# DRV8871.net
KiCad netlist of a schematic drawn in EAGLE
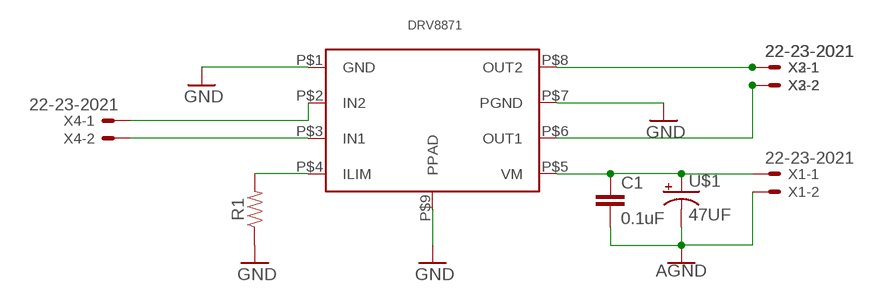
[diagram p0: schematic, sheet 1]

(export (version "E")
  (design (tool "Eeschema 10.0.6"))
  (components
    (comp (ref "C1")
      (value "0.1uF")
      (footprint "eagle-import:0402")
      (libsource (lib "eagle-import") (part "0.1UF-0402-16V-10%"))
    )
    (comp (ref "R1")
      (value "RESISTOR0402")
      (footprint "eagle-import:0402")
      (libsource (lib "eagle-import") (part "RESISTOR0402"))
    )
    (comp (ref "U$1")
      (value "47UF")
      (footprint "eagle-import:UCM1C470MCL1GS")
      (libsource (lib "eagle-import") (part "47UF"))
    )
    (comp (ref "U1")
      (value "DRV8871")
      (footprint "eagle-import:DDA(R-PDSO-G8)")
      (libsource (lib "eagle-import") (part "DRV8871"))
    )
    (comp (ref "X1")
      (value "22-23-2021")
      (footprint "eagle-import:22-23-2021")
      (fields (field (name "MF") "MOLEX"))
      (libsource (lib "eagle-import") (part "22-23-2021"))
    )
    (comp (ref "X2")
      (value "22-23-2021")
      (footprint "eagle-import:22-23-2021")
      (fields (field (name "MF") "MOLEX"))
      (libsource (lib "eagle-import") (part "22-23-2021"))
    )
    (comp (ref "X3")
      (value "22-23-2021")
      (footprint "eagle-import:22-23-2021")
      (fields (field (name "MF") "MOLEX"))
      (libsource (lib "eagle-import") (part "22-23-2021"))
    )
    (comp (ref "X4")
      (value "22-23-2021")
      (footprint "eagle-import:22-23-2021")
      (fields (field (name "MF") "MOLEX"))
      (libsource (lib "eagle-import") (part "22-23-2021"))
    )
  )
  (nets
    (net (code "1") (name "AGND") (class "Default")
      (node (ref "C1") (pin "2") (pinfunction "2_2") (pintype "passive"))
      (node (ref "U$1") (pin "P$2") (pinfunction "-_P$2") (pintype "passive"))
      (node (ref "X1") (pin "2") (pinfunction "S_2") (pintype "passive"))
    )
    (net (code "2") (name "GND") (class "Default")
      (node (ref "R1") (pin "1") (pinfunction "1_1") (pintype "passive"))
      (node (ref "U1") (pin "P$1") (pinfunction "GND_P$1") (pintype "bidirectional"))
      (node (ref "U1") (pin "P$7") (pinfunction "PGND_P$7") (pintype "bidirectional"))
      (node (ref "U1") (pin "P$9") (pinfunction "PPAD_P$9") (pintype "bidirectional"))
    )
    (net (code "3") (name "Net-(U$1-+)") (class "Default")
      (node (ref "C1") (pin "1") (pinfunction "1_1") (pintype "passive"))
      (node (ref "U$1") (pin "P$1") (pinfunction "+_P$1") (pintype "passive"))
      (node (ref "U1") (pin "P$5") (pinfunction "VM_P$5") (pintype "bidirectional"))
      (node (ref "X1") (pin "1") (pinfunction "S_1") (pintype "passive"))
    )
    (net (code "4") (name "Net-(U1-ILIM)") (class "Default")
      (node (ref "R1") (pin "2") (pinfunction "2_2") (pintype "passive"))
      (node (ref "U1") (pin "P$4") (pinfunction "ILIM_P$4") (pintype "bidirectional"))
    )
    (net (code "5") (name "Net-(U1-IN1)") (class "Default")
      (node (ref "U1") (pin "P$3") (pinfunction "IN1_P$3") (pintype "bidirectional"))
      (node (ref "X4") (pin "2") (pinfunction "S_2") (pintype "passive"))
    )
    (net (code "6") (name "Net-(U1-IN2)") (class "Default")
      (node (ref "U1") (pin "P$2") (pinfunction "IN2_P$2") (pintype "bidirectional"))
      (node (ref "X4") (pin "1") (pinfunction "S_1") (pintype "passive"))
    )
    (net (code "7") (name "Net-(U1-OUT1)") (class "Default")
      (node (ref "U1") (pin "P$6") (pinfunction "OUT1_P$6") (pintype "bidirectional"))
      (node (ref "X2") (pin "2") (pinfunction "S_2") (pintype "passive"))
      (node (ref "X3") (pin "2") (pinfunction "S_2") (pintype "passive"))
    )
    (net (code "8") (name "Net-(U1-OUT2)") (class "Default")
      (node (ref "U1") (pin "P$8") (pinfunction "OUT2_P$8") (pintype "bidirectional"))
      (node (ref "X2") (pin "1") (pinfunction "S_1") (pintype "passive"))
      (node (ref "X3") (pin "1") (pinfunction "S_1") (pintype "passive"))
    )
  )
)
